# 5V_to_3v3_LDO.net
KiCad netlist of a schematic drawn in Altium Designer
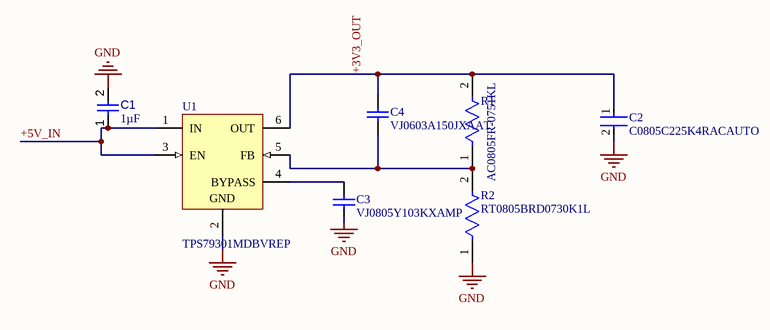
[diagram p0: 5V_to_3v3_LDO.SchDoc]

(export (version "E")
  (design (tool "Eeschema 10.0.6"))
  (components
    (comp (ref "C1")
      (value "1µF")
      (footprint "CAPC2013X145X50ML20T25")
      (description "Chip Capacitor, 1 uF, +/-10%, 25 V, 0805 (2012 Metric)")
      (fields (field (name "TOLERANCE") "10%") (field (name "Comment") "Capacitor 1 uF +/- 10% 25 V 0805"))
      (libsource (lib "vavila") (part "CAP-NP-2"))
    )
    (comp (ref "C2")
      (value "C0805C225K4RACAUTO")
      (footprint "FP-C0805C225K4RACAUTO-MFG")
      (description "CAP CER 2.2UF 16V X7R 0805")
      (fields (field (name "TOLERANCE") "10%"))
      (libsource (lib "Altium Content Vault") (part "b4654b650e69147ec39a6b967a45e02"))
    )
    (comp (ref "C3")
      (value "VJ0805Y103KXAMP")
      (footprint "CAPC2013X145X48LL20T23")
      (fields (field (name "MANUFACTURER") "Vitramon"))
      (libsource (lib "Altium Content Vault") (part "CAP"))
    )
    (comp (ref "C4")
      (value "VJ0603A150JXAAT")
      (footprint "CAPC1608X92X38NL15T08")
      (fields (field (name "MANUFACTURER") "Vitramon"))
      (libsource (lib "Altium Content Vault") (part "CAP"))
    )
    (comp (ref "R1")
      (value "AC0805FR-0751KL")
      (footprint "FP-AC0805-MFG")
      (description "RES SMD 51K OHM 1% 1/8W 0805")
      (fields
        (field (name "MANUFACTURER") "Yageo")
        (field (name "OCTOPART") "https://octopart.com/ac0805fr-0751kl-yageo-24874955")
      )
      (libsource (lib "Altium Content Vault") (part "1029c3af85768c4190bb7ad29bc67b5"))
    )
    (comp (ref "R2")
      (value "RT0805BRD0730K1L")
      (footprint "FP-RT0805-MFG")
      (description "RES SMD 30.1K OHM 0.1% 1/8W 0805")
      (fields
        (field (name "OCTOPART") "https://octopart.com/rt0805brd0730k1l-yageo-1452498")
        (field (name "TOLERANCE") "0.0025")
      )
      (libsource (lib "Altium Content Vault") (part "1029c3af85768c4190bb7ad29bc67b5"))
    )
    (comp (ref "U1")
      (value "TPS79301MDBVREP")
      (footprint "DBV0006A_L")
      (fields (field (name "MANUFACTURER") "Texas Instruments"))
      (libsource (lib "Altium Content Vault") (part "TI-TPS79X01-DBV6"))
    )
  )
  (nets
    (net (code "1") (name "/+3V3_OUT") (class "Default")
      (node (ref "C2") (pin "1") (pinfunction "1_1") (pintype "passive"))
      (node (ref "C4") (pin "1") (pinfunction "1_1") (pintype "passive"))
      (node (ref "R1") (pin "2") (pinfunction "2_2") (pintype "passive"))
      (node (ref "U1") (pin "6") (pinfunction "OUT_6") (pintype "power_in"))
    )
    (net (code "2") (name "/+5V_IN") (class "Default")
      (node (ref "C1") (pin "1") (pinfunction "1_1") (pintype "passive"))
      (node (ref "U1") (pin "1") (pinfunction "IN_1") (pintype "power_in"))
      (node (ref "U1") (pin "3") (pinfunction "EN_3") (pintype "input"))
    )
    (net (code "3") (name "GND") (class "Default")
      (node (ref "C1") (pin "2") (pinfunction "2_2") (pintype "passive"))
      (node (ref "C2") (pin "2") (pinfunction "2_2") (pintype "passive"))
      (node (ref "C3") (pin "2") (pinfunction "2_2") (pintype "passive"))
      (node (ref "R2") (pin "1") (pinfunction "1_1") (pintype "passive"))
      (node (ref "U1") (pin "2") (pinfunction "GND_2") (pintype "power_in"))
    )
    (net (code "4") (name "Net-(U1-BYPASS)") (class "Default")
      (node (ref "C3") (pin "1") (pinfunction "1_1") (pintype "passive"))
      (node (ref "U1") (pin "4") (pinfunction "BYPASS_4") (pintype "passive"))
    )
    (net (code "5") (name "Net-(U1-FB)") (class "Default")
      (node (ref "C4") (pin "2") (pinfunction "2_2") (pintype "passive"))
      (node (ref "R1") (pin "1") (pinfunction "1_1") (pintype "passive"))
      (node (ref "R2") (pin "2") (pinfunction "2_2") (pintype "passive"))
      (node (ref "U1") (pin "5") (pinfunction "FB_5") (pintype "input"))
    )
  )
)
